# motor_pot.net
KiCad netlist of a schematic drawn in EAGLE
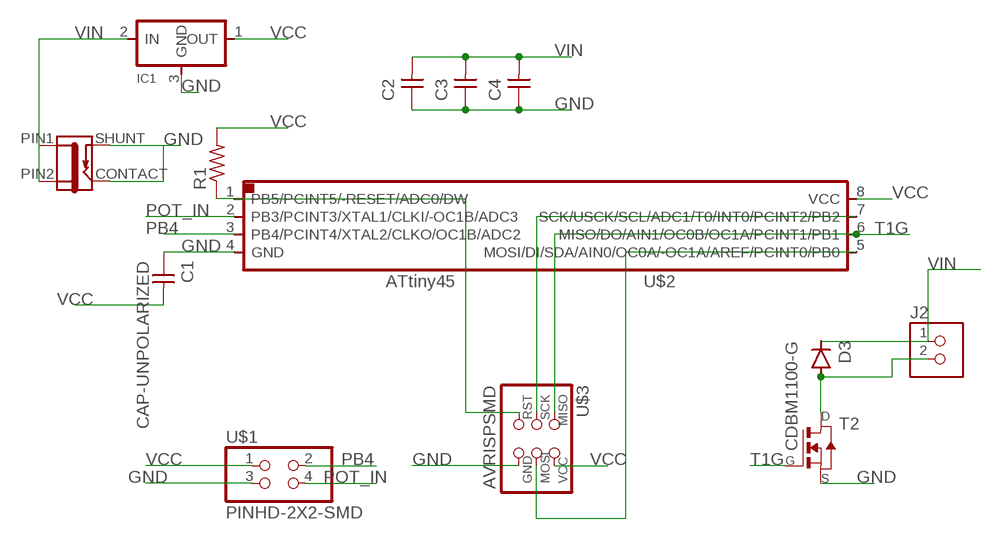
[diagram p0: schematic, sheet 1]

(export (version "E")
  (design (tool "Eeschema 10.0.6"))
  (components
    (comp (ref "C1")
      (value "CAP-UNPOLARIZED")
      (footprint "eagle-import:C1206")
      (libsource (lib "eagle-import") (part "fab copy_CAP-UNPOLARIZED"))
    )
    (comp (ref "C2")
      (value "CAP-UNPOLARIZED")
      (footprint "eagle-import:C1206")
      (libsource (lib "eagle-import") (part "CAP-UNPOLARIZED"))
    )
    (comp (ref "C3")
      (value "CAP-UNPOLARIZED")
      (footprint "eagle-import:C1206")
      (libsource (lib "eagle-import") (part "CAP-UNPOLARIZED"))
    )
    (comp (ref "C4")
      (value "CAP-UNPOLARIZED")
      (footprint "eagle-import:C1206")
      (libsource (lib "eagle-import") (part "CAP-UNPOLARIZED"))
    )
    (comp (ref "D3")
      (value "CDBM1100-G")
      (footprint "eagle-import:MINI-SMA")
      (libsource (lib "eagle-import") (part "CDBM1100-G"))
    )
    (comp (ref "IC1")
      (value "REGULATORSOT23")
      (footprint "eagle-import:SOT23")
      (libsource (lib "eagle-import") (part "REGULATORSOT23"))
    )
    (comp (ref "J2")
      (value "TERM-1X02-FABLAB")
      (footprint "eagle-import:ED555DS-2DS")
      (libsource (lib "eagle-import") (part "TERM-1X02-FABLAB"))
    )
    (comp (ref "J3")
      (value "JACK-2.1MM")
      (footprint "eagle-import:PJ-002AH-SMT")
      (libsource (lib "eagle-import") (part "JACK-2.1MM"))
    )
    (comp (ref "R1")
      (value "RES-US1206")
      (footprint "eagle-import:R1206")
      (libsource (lib "eagle-import") (part "RES-US1206"))
    )
    (comp (ref "T2")
      (value "NMOSFETTO252")
      (footprint "eagle-import:TO252")
      (libsource (lib "eagle-import") (part "NMOSFETTO252"))
    )
    (comp (ref "U$1")
      (value "PINHD-2X2-SMD")
      (footprint "eagle-import:2X02SMD")
      (libsource (lib "eagle-import") (part "PINHD-2X2-SMD"))
    )
    (comp (ref "U$2")
      (value "ATTINY45SI")
      (footprint "eagle-import:SOIC8")
      (libsource (lib "eagle-import") (part "ATTINY45SI"))
    )
    (comp (ref "U$3")
      (value "AVRISPSMD")
      (footprint "eagle-import:2X03SMD")
      (libsource (lib "eagle-import") (part "AVRISPSMD"))
    )
  )
  (nets
    (net (code "1") (name "/GND") (class "Default")
      (node (ref "C1") (pin "1") (pinfunction "1_1") (pintype "passive"))
      (node (ref "C2") (pin "1") (pinfunction "1_1") (pintype "passive"))
      (node (ref "C3") (pin "1") (pinfunction "1_1") (pintype "passive"))
      (node (ref "C4") (pin "1") (pinfunction "1_1") (pintype "passive"))
      (node (ref "IC1") (pin "3") (pinfunction "GND_3") (pintype "bidirectional"))
      (node (ref "J3") (pin "CONTACT") (pinfunction "CONTACT_CONTACT") (pintype "power_in"))
      (node (ref "J3") (pin "SHUNT") (pinfunction "SHUNT_SHUNT") (pintype "power_in"))
      (node (ref "T2") (pin "2") (pinfunction "S_2") (pintype "passive"))
      (node (ref "U$1") (pin "3") (pinfunction "3_3") (pintype "passive"))
      (node (ref "U$2") (pin "4") (pinfunction "GND_4") (pintype "bidirectional"))
      (node (ref "U$3") (pin "6") (pinfunction "GND_6") (pintype "passive"))
    )
    (net (code "2") (name "/PB4") (class "Default")
      (node (ref "U$1") (pin "2") (pinfunction "2_2") (pintype "passive"))
      (node (ref "U$2") (pin "3") (pinfunction "PB4/PCINT4/XTAL2/CLKO/OC1B/ADC2_3") (pintype "bidirectional"))
    )
    (net (code "3") (name "/POT_IN") (class "Default")
      (node (ref "U$1") (pin "4") (pinfunction "4_4") (pintype "passive"))
      (node (ref "U$2") (pin "2") (pinfunction "PB3/PCINT3/XTAL1/CLKI/-OC1B/ADC3_2") (pintype "bidirectional"))
    )
    (net (code "4") (name "/T1G") (class "Default")
      (node (ref "T2") (pin "1") (pinfunction "G_1") (pintype "passive"))
      (node (ref "U$2") (pin "6") (pinfunction "MISO/DO/AIN1/OC0B/OC1A/PCINT1/PB1_6") (pintype "bidirectional"))
      (node (ref "U$3") (pin "1") (pinfunction "MISO_1") (pintype "passive"))
    )
    (net (code "5") (name "/VCC") (class "Default")
      (node (ref "C1") (pin "2") (pinfunction "2_2") (pintype "passive"))
      (node (ref "IC1") (pin "1") (pinfunction "OUT_1") (pintype "bidirectional"))
      (node (ref "R1") (pin "2") (pinfunction "2_2") (pintype "passive"))
      (node (ref "U$1") (pin "1") (pinfunction "1_1") (pintype "passive"))
      (node (ref "U$2") (pin "8") (pinfunction "VCC_8") (pintype "bidirectional"))
      (node (ref "U$3") (pin "2") (pinfunction "VCC_2") (pintype "passive"))
    )
    (net (code "6") (name "/VIN") (class "Default")
      (node (ref "C2") (pin "2") (pinfunction "2_2") (pintype "passive"))
      (node (ref "C3") (pin "2") (pinfunction "2_2") (pintype "passive"))
      (node (ref "C4") (pin "2") (pinfunction "2_2") (pintype "passive"))
      (node (ref "D3") (pin "KATHODE") (pinfunction "KATHODE_KATHODE") (pintype "bidirectional"))
      (node (ref "IC1") (pin "2") (pinfunction "IN_2") (pintype "bidirectional"))
      (node (ref "J2") (pin "1") (pinfunction "1_1") (pintype "passive"))
      (node (ref "J3") (pin "PIN1") (pinfunction "PIN1_PIN1") (pintype "power_in"))
      (node (ref "J3") (pin "PIN2") (pinfunction "PIN2_PIN2") (pintype "power_in"))
    )
    (net (code "7") (name "Net-(T2-D)") (class "Default")
      (node (ref "D3") (pin "ANODE") (pinfunction "ANODE_ANODE") (pintype "bidirectional"))
      (node (ref "J2") (pin "2") (pinfunction "2_2") (pintype "passive"))
      (node (ref "T2") (pin "3") (pinfunction "D_3") (pintype "passive"))
    )
    (net (code "8") (name "Net-(U$2-MOSI{slash}DI{slash}SDA{slash}AIN0{slash}OC0A{slash}-OC1A{slash}AREF{slash}PCINT0{slash}PB0)") (class "Default")
      (node (ref "U$2") (pin "5") (pinfunction "MOSI/DI/SDA/AIN0/OC0A/-OC1A/AREF/PCINT0/PB0_5") (pintype "bidirectional"))
      (node (ref "U$3") (pin "4") (pinfunction "MOSI_4") (pintype "passive"))
    )
    (net (code "9") (name "Net-(U$2-PB5{slash}PCINT5{slash}-RESET{slash}ADC0{slash}DW)") (class "Default")
      (node (ref "R1") (pin "1") (pinfunction "1_1") (pintype "passive"))
      (node (ref "U$2") (pin "1") (pinfunction "PB5/PCINT5/-RESET/ADC0/DW_1") (pintype "bidirectional"))
      (node (ref "U$3") (pin "5") (pinfunction "RST_5") (pintype "passive"))
    )
    (net (code "10") (name "Net-(U$2-SCK{slash}USCK{slash}SCL{slash}ADC1{slash}T0{slash}INT0{slash}PCINT2{slash}PB2)") (class "Default")
      (node (ref "U$2") (pin "7") (pinfunction "SCK/USCK/SCL/ADC1/T0/INT0/PCINT2/PB2_7") (pintype "bidirectional"))
      (node (ref "U$3") (pin "3") (pinfunction "SCK_3") (pintype "passive"))
    )
  )
)
